# LCD.net
KiCad netlist of a schematic drawn in Altium Designer
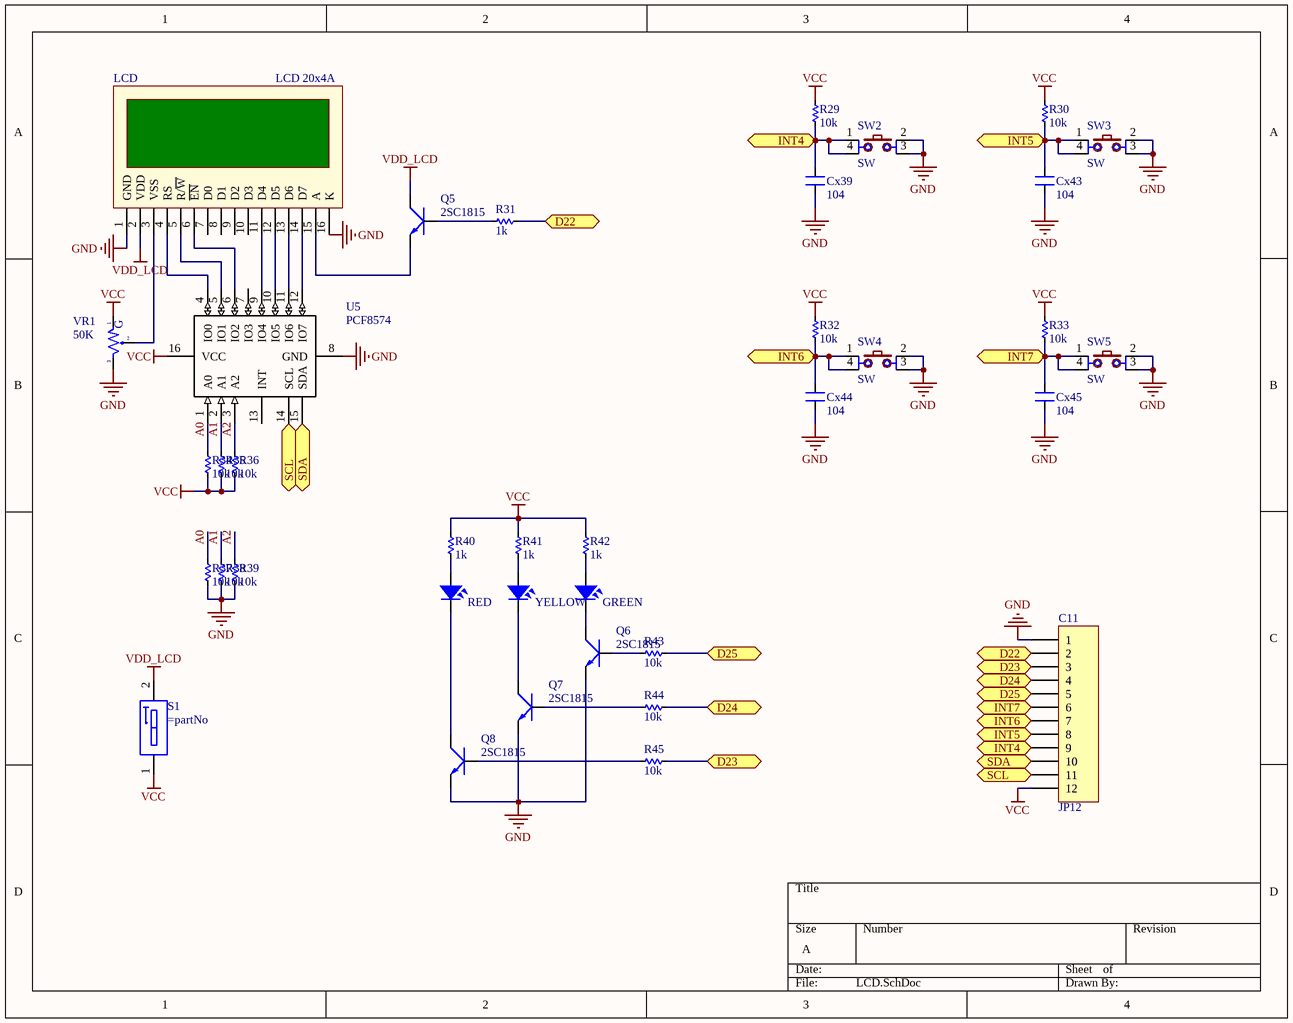
[diagram p0: LCD.SchDoc]

(export (version "E")
  (design (tool "Eeschema 10.0.6"))
  (components
    (comp (ref "C11")
      (value "JP12")
      (footprint "JP12-D1C")
      (description "WR-PHD 2.54 mm Angled Socket Header")
      (fields
        (field (name "MANUFACTURER") "Würth Elektronik eiSos GmbH")
        (field (name "PARTNO") "613012143121")
        (field (name "CREATED BY") "Karrer Zheng")
      )
      (libsource (lib "LIBRARY") (part "JP12"))
    )
    (comp (ref "Cx39") (value "104") (footprint "CN-SMD-0805") (libsource (lib "LIBRARY") (part "CN")))
    (comp (ref "Cx43") (value "104") (footprint "CN-SMD-0805") (libsource (lib "LIBRARY") (part "CN")))
    (comp (ref "Cx44") (value "104") (footprint "CN-SMD-0805") (libsource (lib "LIBRARY") (part "CN")))
    (comp (ref "Cx45") (value "104") (footprint "CN-SMD-0805") (libsource (lib "LIBRARY") (part "CN")))
    (comp (ref "GREEN")
      (value "LED")
      (footprint "LED-5-Green")
      (description "LED Single colour Green and Red")
      (libsource (lib "LIBRARY") (part "LED"))
    )
    (comp (ref "LCD")
      (value "LCD 20x4A")
      (footprint "LCD20X4A")
      (description "LCD dipslay 20 char, 4 line")
      (libsource (lib "LIBRARY") (part "LCD20x4A"))
    )
    (comp (ref "Q5")
      (value "2SC1815")
      (footprint "SOT23-321")
      (description "NPN 600mW, ECB")
      (libsource (lib "LIBRARY") (part "2SC1815"))
    )
    (comp (ref "Q6")
      (value "2SC1815")
      (footprint "SOT23-321")
      (description "NPN 600mW, ECB")
      (libsource (lib "LIBRARY") (part "2SC1815"))
    )
    (comp (ref "Q7")
      (value "2SC1815")
      (footprint "SOT23-321")
      (description "NPN 600mW, ECB")
      (libsource (lib "LIBRARY") (part "2SC1815"))
    )
    (comp (ref "Q8")
      (value "2SC1815")
      (footprint "SOT23-321")
      (description "NPN 600mW, ECB")
      (libsource (lib "LIBRARY") (part "2SC1815"))
    )
    (comp (ref "R29")
      (value "10k")
      (footprint "RES-SMD-0805")
      (description "Resistor")
      (fields
        (field (name "MANUFACTURER") "Generic Components")
        (field (name "PUBLISHER") "Altium Hobart Technology Centre")
      )
      (libsource (lib "LIBRARY") (part "Res-SMD"))
    )
    (comp (ref "R30")
      (value "10k")
      (footprint "RES-SMD-0805")
      (description "Resistor")
      (fields
        (field (name "MANUFACTURER") "Generic Components")
        (field (name "PUBLISHER") "Altium Hobart Technology Centre")
      )
      (libsource (lib "LIBRARY") (part "Res-SMD"))
    )
    (comp (ref "R31")
      (value "1k")
      (footprint "RES-SMD-0805")
      (description "Resistor")
      (fields
        (field (name "MANUFACTURER") "Generic Components")
        (field (name "PUBLISHER") "Altium Hobart Technology Centre")
      )
      (libsource (lib "LIBRARY") (part "Res-SMD"))
    )
    (comp (ref "R32")
      (value "10k")
      (footprint "RES-SMD-0805")
      (description "Resistor")
      (fields
        (field (name "MANUFACTURER") "Generic Components")
        (field (name "PUBLISHER") "Altium Hobart Technology Centre")
      )
      (libsource (lib "LIBRARY") (part "Res-SMD"))
    )
    (comp (ref "R33")
      (value "10k")
      (footprint "RES-SMD-0805")
      (description "Resistor")
      (fields
        (field (name "MANUFACTURER") "Generic Components")
        (field (name "PUBLISHER") "Altium Hobart Technology Centre")
      )
      (libsource (lib "LIBRARY") (part "Res-SMD"))
    )
    (comp (ref "R34")
      (value "10k")
      (footprint "RES-SMD-0805")
      (description "Resistor")
      (fields
        (field (name "MANUFACTURER") "Generic Components")
        (field (name "PUBLISHER") "Altium Hobart Technology Centre")
      )
      (libsource (lib "LIBRARY") (part "Res-SMD"))
    )
    (comp (ref "R35")
      (value "10k")
      (footprint "RES-SMD-0805")
      (description "Resistor")
      (fields
        (field (name "MANUFACTURER") "Generic Components")
        (field (name "PUBLISHER") "Altium Hobart Technology Centre")
      )
      (libsource (lib "LIBRARY") (part "Res-SMD"))
    )
    (comp (ref "R36")
      (value "10k")
      (footprint "RES-SMD-0805")
      (description "Resistor")
      (fields
        (field (name "MANUFACTURER") "Generic Components")
        (field (name "PUBLISHER") "Altium Hobart Technology Centre")
      )
      (libsource (lib "LIBRARY") (part "Res-SMD"))
    )
    (comp (ref "R37")
      (value "10k")
      (footprint "RES-SMD-0805")
      (description "Resistor")
      (fields
        (field (name "MANUFACTURER") "Generic Components")
        (field (name "PUBLISHER") "Altium Hobart Technology Centre")
      )
      (libsource (lib "LIBRARY") (part "Res-SMD"))
    )
    (comp (ref "R38")
      (value "10k")
      (footprint "RES-SMD-0805")
      (description "Resistor")
      (fields
        (field (name "MANUFACTURER") "Generic Components")
        (field (name "PUBLISHER") "Altium Hobart Technology Centre")
      )
      (libsource (lib "LIBRARY") (part "Res-SMD"))
    )
    (comp (ref "R39")
      (value "10k")
      (footprint "RES-SMD-0805")
      (description "Resistor")
      (fields
        (field (name "MANUFACTURER") "Generic Components")
        (field (name "PUBLISHER") "Altium Hobart Technology Centre")
      )
      (libsource (lib "LIBRARY") (part "Res-SMD"))
    )
    (comp (ref "R40")
      (value "1k")
      (footprint "RES-SMD-0805")
      (description "Resistor")
      (fields
        (field (name "MANUFACTURER") "Generic Components")
        (field (name "PUBLISHER") "Altium Hobart Technology Centre")
      )
      (libsource (lib "LIBRARY") (part "Res-SMD"))
    )
    (comp (ref "R41")
      (value "1k")
      (footprint "RES-SMD-0805")
      (description "Resistor")
      (fields
        (field (name "MANUFACTURER") "Generic Components")
        (field (name "PUBLISHER") "Altium Hobart Technology Centre")
      )
      (libsource (lib "LIBRARY") (part "Res-SMD"))
    )
    (comp (ref "R42")
      (value "1k")
      (footprint "RES-SMD-0805")
      (description "Resistor")
      (fields
        (field (name "MANUFACTURER") "Generic Components")
        (field (name "PUBLISHER") "Altium Hobart Technology Centre")
      )
      (libsource (lib "LIBRARY") (part "Res-SMD"))
    )
    (comp (ref "R43")
      (value "10k")
      (footprint "RES-SMD-0805")
      (description "Resistor")
      (fields
        (field (name "MANUFACTURER") "Generic Components")
        (field (name "PUBLISHER") "Altium Hobart Technology Centre")
      )
      (libsource (lib "LIBRARY") (part "Res-SMD"))
    )
    (comp (ref "R44")
      (value "10k")
      (footprint "RES-SMD-0805")
      (description "Resistor")
      (fields
        (field (name "MANUFACTURER") "Generic Components")
        (field (name "PUBLISHER") "Altium Hobart Technology Centre")
      )
      (libsource (lib "LIBRARY") (part "Res-SMD"))
    )
    (comp (ref "R45")
      (value "10k")
      (footprint "RES-SMD-0805")
      (description "Resistor")
      (fields
        (field (name "MANUFACTURER") "Generic Components")
        (field (name "PUBLISHER") "Altium Hobart Technology Centre")
      )
      (libsource (lib "LIBRARY") (part "Res-SMD"))
    )
    (comp (ref "RED")
      (value "LED")
      (footprint "LED-5-RED")
      (description "LED Single colour Green and Red")
      (libsource (lib "LIBRARY") (part "LED"))
    )
    (comp (ref "S1")
      (value "~")
      (footprint "SW-DIP1")
      (description "WS-DITV 2.54 mm small compact THT flat actuator with top tape")
      (fields
        (field (name "MANUFACTURER") "Wurth Elektronik")
        (field (name "PART NO.") "418127160901")
        (field (name "CREATED BY") "Baojun Chen")
      )
      (libsource (lib "LIBRARY") (part "SWDIP1"))
    )
    (comp (ref "SW2")
      (value "SW")
      (footprint "SW2-DIP")
      (description "Switch button 4 pin")
      (libsource (lib "LIBRARY") (part "SW4"))
    )
    (comp (ref "SW3")
      (value "SW")
      (footprint "SW2-DIP")
      (description "Switch button 4 pin")
      (libsource (lib "LIBRARY") (part "SW4"))
    )
    (comp (ref "SW4")
      (value "SW")
      (footprint "SW2-DIP")
      (description "Switch button 4 pin")
      (libsource (lib "LIBRARY") (part "SW4"))
    )
    (comp (ref "SW5")
      (value "SW")
      (footprint "SW2-DIP")
      (description "Switch button 4 pin")
      (libsource (lib "LIBRARY") (part "SW4"))
    )
    (comp (ref "U5")
      (value "PCF8574")
      (footprint "SO16L")
      (description "I2C PORT EXPANDER")
      (fields
        (field (name "MANUFACTURER PART NUMBER") "PCF8574T/3,512")
        (field (name "MANUFACTURER") "NXP Semiconductors")
      )
      (libsource (lib "LIBRARY") (part "PCF8574"))
    )
    (comp (ref "VR1")
      (value "50K")
      (footprint "VR-S2")
      (description "Var Resistor")
      (libsource (lib "LIBRARY") (part "VR-S"))
    )
    (comp (ref "YELLOW")
      (value "LED")
      (footprint "LED-5-Yellow")
      (description "LED Single colour Green and Red")
      (libsource (lib "LIBRARY") (part "LED"))
    )
  )
  (nets
    (net (code "1") (name "/A0") (class "Default")
      (node (ref "R34") (pin "1") (pinfunction "1_1") (pintype "passive"))
      (node (ref "R37") (pin "1") (pinfunction "1_1") (pintype "passive"))
      (node (ref "U5") (pin "1") (pinfunction "A0_1") (pintype "input"))
    )
    (net (code "2") (name "/A1") (class "Default")
      (node (ref "R35") (pin "1") (pinfunction "1_1") (pintype "passive"))
      (node (ref "R38") (pin "1") (pinfunction "1_1") (pintype "passive"))
      (node (ref "U5") (pin "2") (pinfunction "A1_2") (pintype "input"))
    )
    (net (code "3") (name "/A2") (class "Default")
      (node (ref "R36") (pin "1") (pinfunction "1_1") (pintype "passive"))
      (node (ref "R39") (pin "1") (pinfunction "1_1") (pintype "passive"))
      (node (ref "U5") (pin "3") (pinfunction "A2_3") (pintype "input"))
    )
    (net (code "4") (name "/D22") (class "Default")
      (node (ref "C11") (pin "2") (pinfunction "2_2") (pintype "passive"))
      (node (ref "R31") (pin "2") (pinfunction "2_2") (pintype "passive"))
    )
    (net (code "5") (name "/D23") (class "Default")
      (node (ref "C11") (pin "3") (pinfunction "3_3") (pintype "passive"))
      (node (ref "R45") (pin "2") (pinfunction "2_2") (pintype "passive"))
    )
    (net (code "6") (name "/D24") (class "Default")
      (node (ref "C11") (pin "4") (pinfunction "4_4") (pintype "passive"))
      (node (ref "R44") (pin "2") (pinfunction "2_2") (pintype "passive"))
    )
    (net (code "7") (name "/D25") (class "Default")
      (node (ref "C11") (pin "5") (pinfunction "5_5") (pintype "passive"))
      (node (ref "R43") (pin "2") (pinfunction "2_2") (pintype "passive"))
    )
    (net (code "8") (name "/INT4") (class "Default")
      (node (ref "C11") (pin "9") (pinfunction "9_9") (pintype "passive"))
      (node (ref "Cx39") (pin "2") (pinfunction "2_2") (pintype "passive"))
      (node (ref "R29") (pin "1") (pinfunction "1_1") (pintype "passive"))
      (node (ref "SW2") (pin "1") (pintype "passive"))
      (node (ref "SW2") (pin "4") (pinfunction "4_4") (pintype "passive"))
    )
    (net (code "9") (name "/INT5") (class "Default")
      (node (ref "C11") (pin "8") (pinfunction "8_8") (pintype "passive"))
      (node (ref "Cx43") (pin "2") (pinfunction "2_2") (pintype "passive"))
      (node (ref "R30") (pin "1") (pinfunction "1_1") (pintype "passive"))
      (node (ref "SW3") (pin "1") (pintype "passive"))
      (node (ref "SW3") (pin "4") (pinfunction "4_4") (pintype "passive"))
    )
    (net (code "10") (name "/INT6") (class "Default")
      (node (ref "C11") (pin "7") (pinfunction "7_7") (pintype "passive"))
      (node (ref "Cx44") (pin "2") (pinfunction "2_2") (pintype "passive"))
      (node (ref "R32") (pin "1") (pinfunction "1_1") (pintype "passive"))
      (node (ref "SW4") (pin "1") (pintype "passive"))
      (node (ref "SW4") (pin "4") (pinfunction "4_4") (pintype "passive"))
    )
    (net (code "11") (name "/INT7") (class "Default")
      (node (ref "C11") (pin "6") (pinfunction "6_6") (pintype "passive"))
      (node (ref "Cx45") (pin "2") (pinfunction "2_2") (pintype "passive"))
      (node (ref "R33") (pin "1") (pinfunction "1_1") (pintype "passive"))
      (node (ref "SW5") (pin "1") (pintype "passive"))
      (node (ref "SW5") (pin "4") (pinfunction "4_4") (pintype "passive"))
    )
    (net (code "12") (name "/SCL") (class "Default")
      (node (ref "C11") (pin "11") (pinfunction "11_11") (pintype "passive"))
      (node (ref "U5") (pin "14") (pinfunction "SCL_14") (pintype "open_collector"))
    )
    (net (code "13") (name "/SDA") (class "Default")
      (node (ref "C11") (pin "10") (pinfunction "10_10") (pintype "passive"))
      (node (ref "U5") (pin "15") (pinfunction "SDA_15") (pintype "open_collector"))
    )
    (net (code "14") (name "GND") (class "Default")
      (node (ref "C11") (pin "1") (pinfunction "1_1") (pintype "passive"))
      (node (ref "Cx39") (pin "1") (pinfunction "1_1") (pintype "passive"))
      (node (ref "Cx43") (pin "1") (pinfunction "1_1") (pintype "passive"))
      (node (ref "Cx44") (pin "1") (pinfunction "1_1") (pintype "passive"))
      (node (ref "Cx45") (pin "1") (pinfunction "1_1") (pintype "passive"))
      (node (ref "LCD") (pin "1") (pinfunction "GND_1") (pintype "passive"))
      (node (ref "LCD") (pin "16") (pinfunction "K_16") (pintype "passive"))
      (node (ref "Q6") (pin "1") (pinfunction "E_1") (pintype "passive"))
      (node (ref "Q7") (pin "1") (pinfunction "E_1") (pintype "passive"))
      (node (ref "Q8") (pin "1") (pinfunction "E_1") (pintype "passive"))
      (node (ref "R37") (pin "2") (pinfunction "2_2") (pintype "passive"))
      (node (ref "R38") (pin "2") (pinfunction "2_2") (pintype "passive"))
      (node (ref "R39") (pin "2") (pinfunction "2_2") (pintype "passive"))
      (node (ref "SW2") (pin "2") (pinfunction "2_2") (pintype "passive"))
      (node (ref "SW2") (pin "3") (pinfunction "3_3") (pintype "passive"))
      (node (ref "SW3") (pin "2") (pinfunction "2_2") (pintype "passive"))
      (node (ref "SW3") (pin "3") (pinfunction "3_3") (pintype "passive"))
      (node (ref "SW4") (pin "2") (pinfunction "2_2") (pintype "passive"))
      (node (ref "SW4") (pin "3") (pinfunction "3_3") (pintype "passive"))
      (node (ref "SW5") (pin "2") (pinfunction "2_2") (pintype "passive"))
      (node (ref "SW5") (pin "3") (pinfunction "3_3") (pintype "passive"))
      (node (ref "U5") (pin "8") (pinfunction "GND_8") (pintype "open_collector"))
      (node (ref "VR1") (pin "3") (pinfunction "3_3") (pintype "passive"))
    )
    (net (code "15") (name "Net-(GREEN-Pad1)") (class "Default")
      (node (ref "GREEN") (pin "1") (pinfunction "1_1") (pintype "passive"))
      (node (ref "R42") (pin "1") (pinfunction "1_1") (pintype "passive"))
    )
    (net (code "16") (name "Net-(LCD-A)") (class "Default")
      (node (ref "LCD") (pin "15") (pinfunction "A_15") (pintype "passive"))
      (node (ref "Q5") (pin "1") (pinfunction "E_1") (pintype "passive"))
    )
    (net (code "17") (name "Net-(LCD-D4)") (class "Default")
      (node (ref "LCD") (pin "11") (pinfunction "D4_11") (pintype "passive"))
      (node (ref "U5") (pin "9") (pinfunction "IO4_9") (pintype "bidirectional"))
    )
    (net (code "18") (name "Net-(LCD-D5)") (class "Default")
      (node (ref "LCD") (pin "12") (pinfunction "D5_12") (pintype "passive"))
      (node (ref "U5") (pin "10") (pinfunction "IO5_10") (pintype "bidirectional"))
    )
    (net (code "19") (name "Net-(LCD-D6)") (class "Default")
      (node (ref "LCD") (pin "13") (pinfunction "D6_13") (pintype "passive"))
      (node (ref "U5") (pin "11") (pinfunction "IO6_11") (pintype "bidirectional"))
    )
    (net (code "20") (name "Net-(LCD-D7)") (class "Default")
      (node (ref "LCD") (pin "14") (pinfunction "D7_14") (pintype "passive"))
      (node (ref "U5") (pin "12") (pinfunction "IO7_12") (pintype "bidirectional"))
    )
    (net (code "21") (name "Net-(LCD-RS)") (class "Default")
      (node (ref "LCD") (pin "4") (pinfunction "RS_4") (pintype "passive"))
      (node (ref "U5") (pin "4") (pinfunction "IO0_4") (pintype "bidirectional"))
    )
    (net (code "22") (name "Net-(LCD-R{slash}~{W})") (class "Default")
      (node (ref "LCD") (pin "5") (pinfunction "R/~{W}_5") (pintype "passive"))
      (node (ref "U5") (pin "5") (pinfunction "IO1_5") (pintype "bidirectional"))
    )
    (net (code "23") (name "Net-(LCD-VSS)") (class "Default")
      (node (ref "LCD") (pin "3") (pinfunction "VSS_3") (pintype "passive"))
      (node (ref "VR1") (pin "2") (pinfunction "2_2") (pintype "passive"))
    )
    (net (code "24") (name "Net-(LCD-~{EN})") (class "Default")
      (node (ref "LCD") (pin "6") (pinfunction "~{EN}_6") (pintype "passive"))
      (node (ref "U5") (pin "6") (pinfunction "IO2_6") (pintype "bidirectional"))
    )
    (net (code "25") (name "Net-(Q5-B)") (class "Default")
      (node (ref "Q5") (pin "3") (pinfunction "B_3") (pintype "passive"))
      (node (ref "R31") (pin "1") (pinfunction "1_1") (pintype "passive"))
    )
    (net (code "26") (name "Net-(Q6-B)") (class "Default")
      (node (ref "Q6") (pin "3") (pinfunction "B_3") (pintype "passive"))
      (node (ref "R43") (pin "1") (pinfunction "1_1") (pintype "passive"))
    )
    (net (code "27") (name "Net-(Q6-C)") (class "Default")
      (node (ref "GREEN") (pin "2") (pinfunction "2_2") (pintype "passive"))
      (node (ref "Q6") (pin "2") (pinfunction "C_2") (pintype "passive"))
    )
    (net (code "28") (name "Net-(Q7-B)") (class "Default")
      (node (ref "Q7") (pin "3") (pinfunction "B_3") (pintype "passive"))
      (node (ref "R44") (pin "1") (pinfunction "1_1") (pintype "passive"))
    )
    (net (code "29") (name "Net-(Q7-C)") (class "Default")
      (node (ref "Q7") (pin "2") (pinfunction "C_2") (pintype "passive"))
      (node (ref "YELLOW") (pin "2") (pinfunction "2_2") (pintype "passive"))
    )
    (net (code "30") (name "Net-(Q8-B)") (class "Default")
      (node (ref "Q8") (pin "3") (pinfunction "B_3") (pintype "passive"))
      (node (ref "R45") (pin "1") (pinfunction "1_1") (pintype "passive"))
    )
    (net (code "31") (name "Net-(Q8-C)") (class "Default")
      (node (ref "Q8") (pin "2") (pinfunction "C_2") (pintype "passive"))
      (node (ref "RED") (pin "2") (pinfunction "2_2") (pintype "passive"))
    )
    (net (code "32") (name "Net-(R40-Pad1)") (class "Default")
      (node (ref "R40") (pin "1") (pinfunction "1_1") (pintype "passive"))
      (node (ref "RED") (pin "1") (pinfunction "1_1") (pintype "passive"))
    )
    (net (code "33") (name "Net-(R41-Pad1)") (class "Default")
      (node (ref "R41") (pin "1") (pinfunction "1_1") (pintype "passive"))
      (node (ref "YELLOW") (pin "1") (pinfunction "1_1") (pintype "passive"))
    )
    (net (code "34") (name "VCC") (class "Default")
      (node (ref "C11") (pin "12") (pinfunction "12_12") (pintype "passive"))
      (node (ref "R29") (pin "2") (pinfunction "2_2") (pintype "passive"))
      (node (ref "R30") (pin "2") (pinfunction "2_2") (pintype "passive"))
      (node (ref "R32") (pin "2") (pinfunction "2_2") (pintype "passive"))
      (node (ref "R33") (pin "2") (pinfunction "2_2") (pintype "passive"))
      (node (ref "R34") (pin "2") (pinfunction "2_2") (pintype "passive"))
      (node (ref "R35") (pin "2") (pinfunction "2_2") (pintype "passive"))
      (node (ref "R36") (pin "2") (pinfunction "2_2") (pintype "passive"))
      (node (ref "R40") (pin "2") (pinfunction "2_2") (pintype "passive"))
      (node (ref "R41") (pin "2") (pinfunction "2_2") (pintype "passive"))
      (node (ref "R42") (pin "2") (pinfunction "2_2") (pintype "passive"))
      (node (ref "S1") (pin "1") (pinfunction "1_1") (pintype "passive"))
      (node (ref "U5") (pin "16") (pinfunction "VCC_16") (pintype "passive"))
      (node (ref "VR1") (pin "1") (pinfunction "1_1") (pintype "passive"))
    )
    (net (code "35") (name "VDD_LCD") (class "Default")
      (node (ref "LCD") (pin "2") (pinfunction "VDD_2") (pintype "passive"))
      (node (ref "Q5") (pin "2") (pinfunction "C_2") (pintype "passive"))
      (node (ref "S1") (pin "2") (pinfunction "2_2") (pintype "passive"))
    )
    (net (code "36") (name "unconnected-(LCD-D0-Pad7)") (class "Default")
      (node (ref "LCD") (pin "7") (pinfunction "D0_7") (pintype "passive"))
    )
    (net (code "37") (name "unconnected-(LCD-D1-Pad8)") (class "Default")
      (node (ref "LCD") (pin "8") (pinfunction "D1_8") (pintype "passive"))
    )
    (net (code "38") (name "unconnected-(LCD-D2-Pad9)") (class "Default")
      (node (ref "LCD") (pin "9") (pinfunction "D2_9") (pintype "passive"))
    )
    (net (code "39") (name "unconnected-(LCD-D3-Pad10)") (class "Default")
      (node (ref "LCD") (pin "10") (pinfunction "D3_10") (pintype "passive"))
    )
    (net (code "40") (name "unconnected-(U5-INT-Pad13)") (class "Default")
      (node (ref "U5") (pin "13") (pinfunction "INT_13") (pintype "open_collector"))
    )
    (net (code "41") (name "unconnected-(U5-IO3-Pad7)") (class "Default")
      (node (ref "U5") (pin "7") (pinfunction "IO3_7") (pintype "bidirectional"))
    )
  )
)
